# RK3399_RGMII_SDIO_SPI_GPIO.net
KiCad netlist of a schematic drawn in Altium Designer
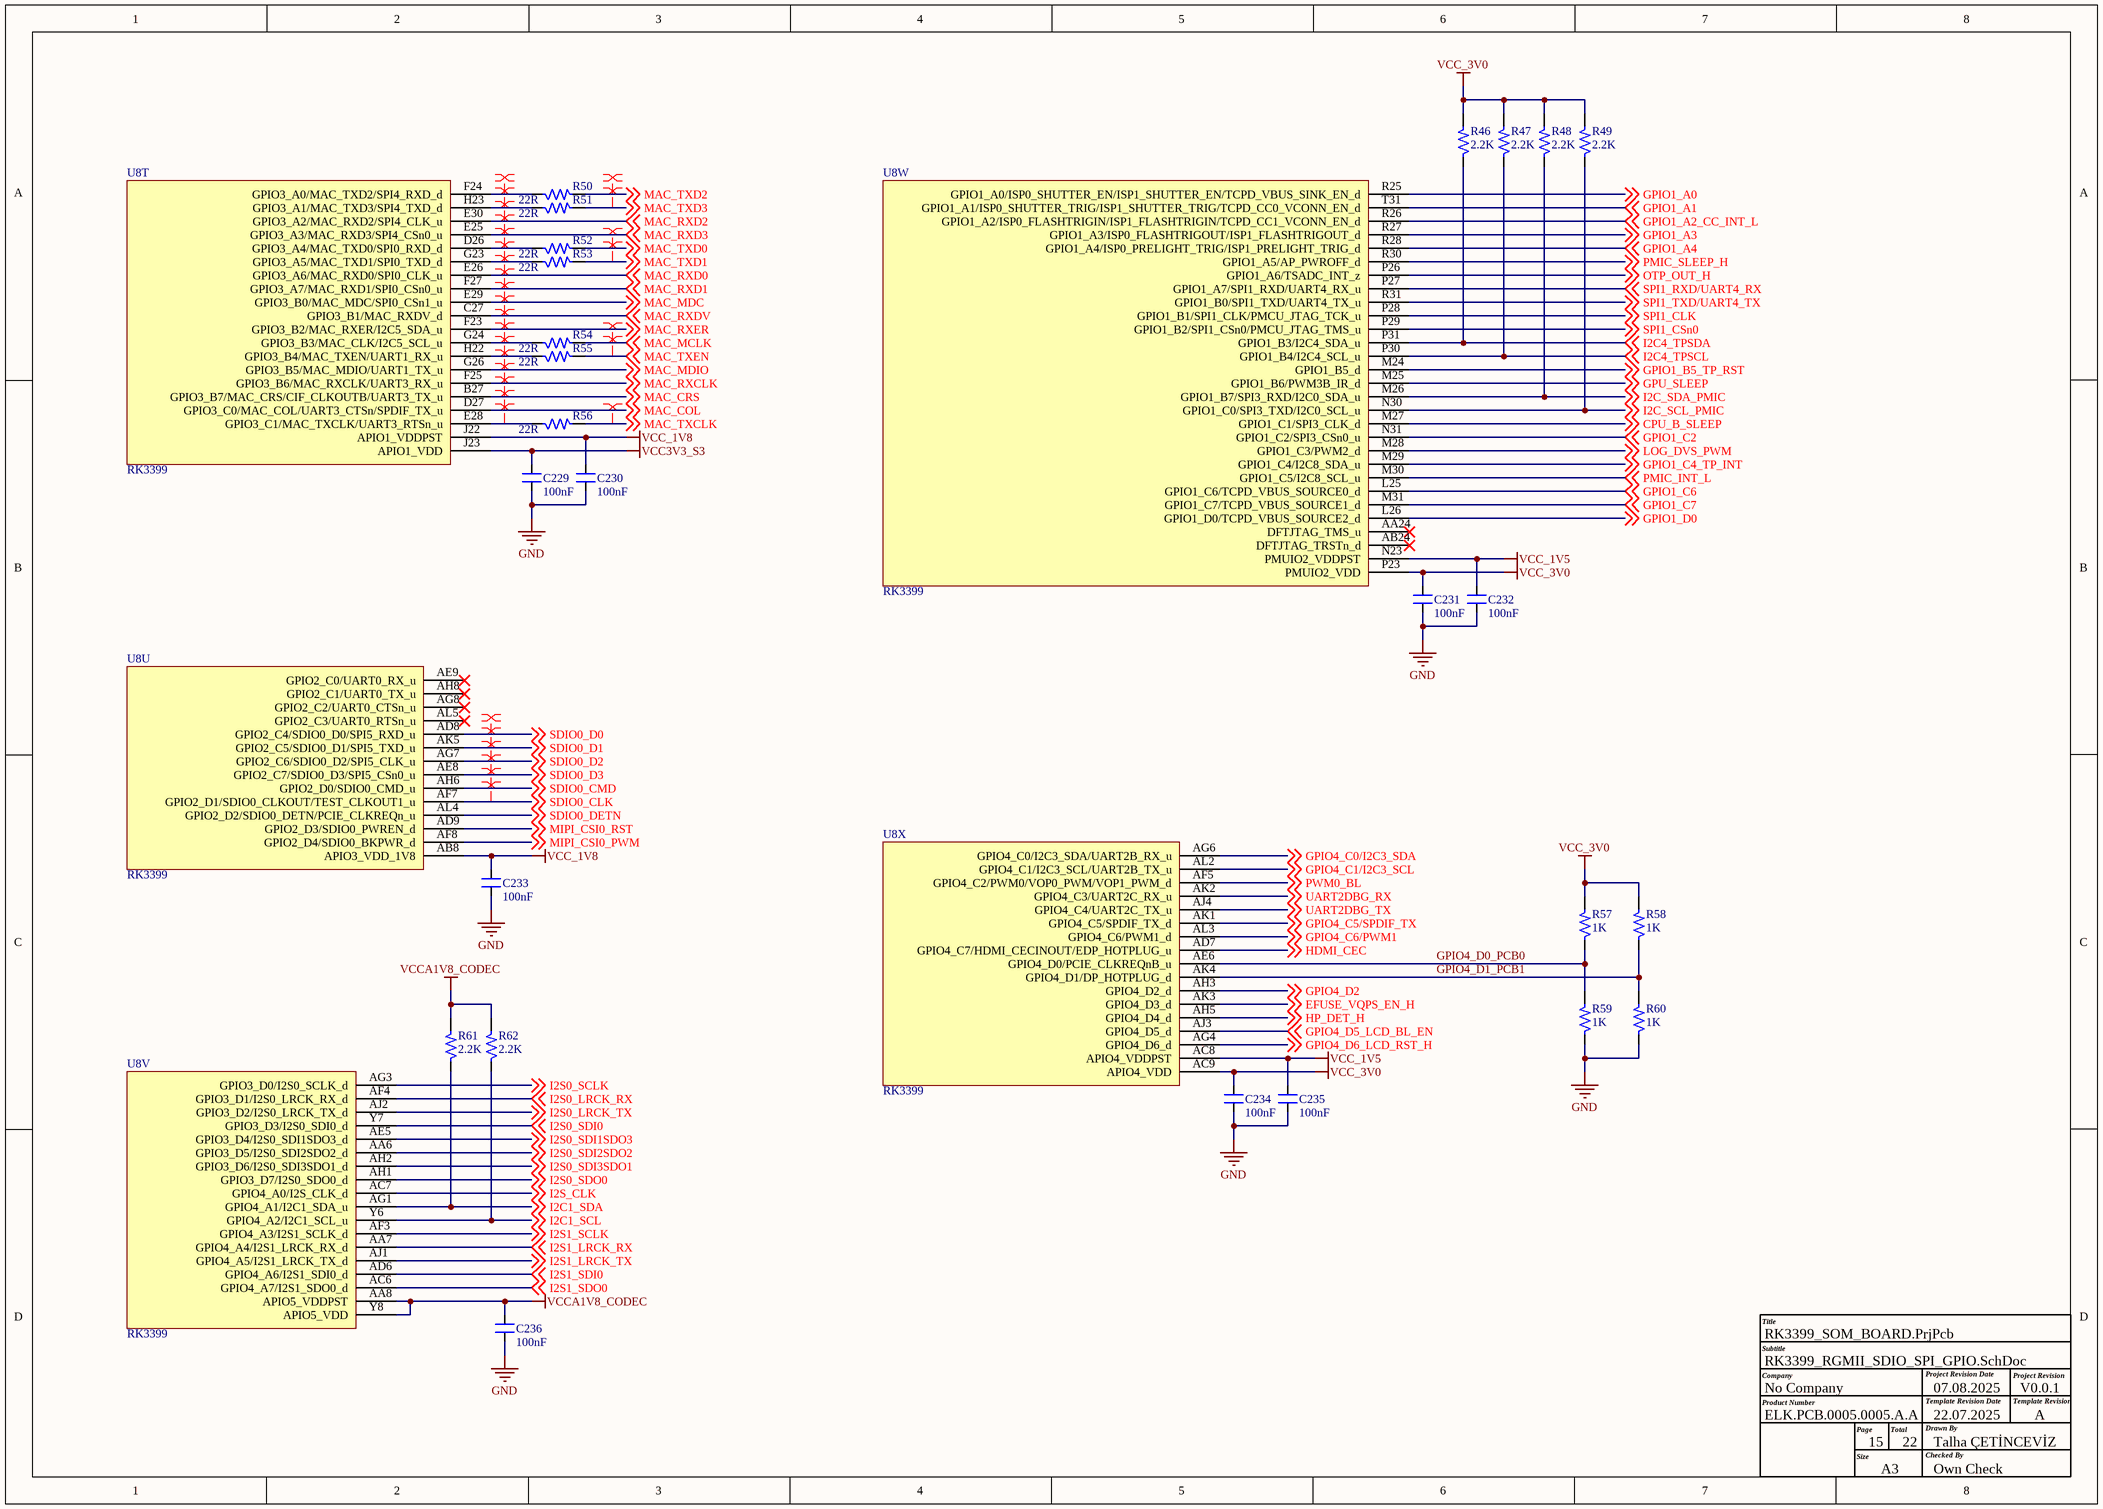
[diagram p0: RK3399_RGMII_SDIO_SPI_GPIO.SchDoc]

(export (version "E")
  (design (tool "Eeschema 10.0.6"))
  (components
    (comp (ref "C229")
      (value "100nF")
      (footprint "CAP_0201")
      (description "0.1µF ±10% 25V Ceramic Capacitor X5R 0201 (0603 Metric)")
      (fields
        (field (name "MANUFACTURER") "TDK Corporation")
        (field (name "MANUFACTURER PART NUMBER") "C0603X5R1E104K030BB")
      )
      (libsource (lib "EsteemPCB_SOM_Course_intlib") (part "CAP_100nF-25V-10%-0201"))
    )
    (comp (ref "C230")
      (value "100nF")
      (footprint "CAP_0201")
      (description "0.1µF ±10% 25V Ceramic Capacitor X5R 0201 (0603 Metric)")
      (fields
        (field (name "MANUFACTURER") "TDK Corporation")
        (field (name "MANUFACTURER PART NUMBER") "C0603X5R1E104K030BB")
      )
      (libsource (lib "EsteemPCB_SOM_Course_intlib") (part "CAP_100nF-25V-10%-0201"))
    )
    (comp (ref "C231")
      (value "100nF")
      (footprint "CAP_0201")
      (description "0.1µF ±10% 25V Ceramic Capacitor X5R 0201 (0603 Metric)")
      (fields
        (field (name "MANUFACTURER") "TDK Corporation")
        (field (name "MANUFACTURER PART NUMBER") "C0603X5R1E104K030BB")
      )
      (libsource (lib "EsteemPCB_SOM_Course_intlib") (part "CAP_100nF-25V-10%-0201"))
    )
    (comp (ref "C232")
      (value "100nF")
      (footprint "CAP_0201")
      (description "0.1µF ±10% 25V Ceramic Capacitor X5R 0201 (0603 Metric)")
      (fields
        (field (name "MANUFACTURER") "TDK Corporation")
        (field (name "MANUFACTURER PART NUMBER") "C0603X5R1E104K030BB")
      )
      (libsource (lib "EsteemPCB_SOM_Course_intlib") (part "CAP_100nF-25V-10%-0201"))
    )
    (comp (ref "C233")
      (value "100nF")
      (footprint "CAP_0201")
      (description "0.1µF ±10% 25V Ceramic Capacitor X5R 0201 (0603 Metric)")
      (fields
        (field (name "MANUFACTURER") "TDK Corporation")
        (field (name "MANUFACTURER PART NUMBER") "C0603X5R1E104K030BB")
      )
      (libsource (lib "EsteemPCB_SOM_Course_intlib") (part "CAP_100nF-25V-10%-0201"))
    )
    (comp (ref "C234")
      (value "100nF")
      (footprint "CAP_0201")
      (description "0.1µF ±10% 25V Ceramic Capacitor X5R 0201 (0603 Metric)")
      (fields
        (field (name "MANUFACTURER") "TDK Corporation")
        (field (name "MANUFACTURER PART NUMBER") "C0603X5R1E104K030BB")
      )
      (libsource (lib "EsteemPCB_SOM_Course_intlib") (part "CAP_100nF-25V-10%-0201"))
    )
    (comp (ref "C235")
      (value "100nF")
      (footprint "CAP_0201")
      (description "0.1µF ±10% 25V Ceramic Capacitor X5R 0201 (0603 Metric)")
      (fields
        (field (name "MANUFACTURER") "TDK Corporation")
        (field (name "MANUFACTURER PART NUMBER") "C0603X5R1E104K030BB")
      )
      (libsource (lib "EsteemPCB_SOM_Course_intlib") (part "CAP_100nF-25V-10%-0201"))
    )
    (comp (ref "C236")
      (value "100nF")
      (footprint "CAP_0201")
      (description "0.1µF ±10% 25V Ceramic Capacitor X5R 0201 (0603 Metric)")
      (fields
        (field (name "MANUFACTURER") "TDK Corporation")
        (field (name "MANUFACTURER PART NUMBER") "C0603X5R1E104K030BB")
      )
      (libsource (lib "EsteemPCB_SOM_Course_intlib") (part "CAP_100nF-25V-10%-0201"))
    )
    (comp (ref "R46")
      (value "2.2K")
      (footprint "RES_0201")
      (description "2.2 kOhms ±1% 0.05W, 1/20W Chip Resistor 0201 (0603 Metric) Thick Film")
      (fields
        (field (name "MANUFACTURER") "Stackpole Electronics Inc")
        (field (name "MANUFACTURER PART NUMBER") "RMCF0201FT2K20")
      )
      (libsource (lib "EsteemPCB_SOM_Course_intlib") (part "RES_2.2K-0.05W-1%-0201"))
    )
    (comp (ref "R47")
      (value "2.2K")
      (footprint "RES_0201")
      (description "2.2 kOhms ±1% 0.05W, 1/20W Chip Resistor 0201 (0603 Metric) Thick Film")
      (fields
        (field (name "MANUFACTURER") "Stackpole Electronics Inc")
        (field (name "MANUFACTURER PART NUMBER") "RMCF0201FT2K20")
      )
      (libsource (lib "EsteemPCB_SOM_Course_intlib") (part "RES_2.2K-0.05W-1%-0201"))
    )
    (comp (ref "R48")
      (value "2.2K")
      (footprint "RES_0201")
      (description "2.2 kOhms ±1% 0.05W, 1/20W Chip Resistor 0201 (0603 Metric) Thick Film")
      (fields
        (field (name "MANUFACTURER") "Stackpole Electronics Inc")
        (field (name "MANUFACTURER PART NUMBER") "RMCF0201FT2K20")
      )
      (libsource (lib "EsteemPCB_SOM_Course_intlib") (part "RES_2.2K-0.05W-1%-0201"))
    )
    (comp (ref "R49")
      (value "2.2K")
      (footprint "RES_0201")
      (description "2.2 kOhms ±1% 0.05W, 1/20W Chip Resistor 0201 (0603 Metric) Thick Film")
      (fields
        (field (name "MANUFACTURER") "Stackpole Electronics Inc")
        (field (name "MANUFACTURER PART NUMBER") "RMCF0201FT2K20")
      )
      (libsource (lib "EsteemPCB_SOM_Course_intlib") (part "RES_2.2K-0.05W-1%-0201"))
    )
    (comp (ref "R50")
      (value "22R")
      (footprint "RES_0201")
      (description "22 Ohms ±1% 0.05W, 1/20W Chip Resistor 0201 (0603 Metric) Moisture Resistant Thick Film")
      (fields
        (field (name "MANUFACTURER") "Yageo")
        (field (name "MANUFACTURER PART NUMBER") "RC0201FR-0722RL")
      )
      (libsource (lib "EsteemPCB_SOM_Course_intlib") (part "RES_22R-0.05W-1%-0201"))
    )
    (comp (ref "R51")
      (value "22R")
      (footprint "RES_0201")
      (description "22 Ohms ±1% 0.05W, 1/20W Chip Resistor 0201 (0603 Metric) Moisture Resistant Thick Film")
      (fields
        (field (name "MANUFACTURER") "Yageo")
        (field (name "MANUFACTURER PART NUMBER") "RC0201FR-0722RL")
      )
      (libsource (lib "EsteemPCB_SOM_Course_intlib") (part "RES_22R-0.05W-1%-0201"))
    )
    (comp (ref "R52")
      (value "22R")
      (footprint "RES_0201")
      (description "22 Ohms ±1% 0.05W, 1/20W Chip Resistor 0201 (0603 Metric) Moisture Resistant Thick Film")
      (fields
        (field (name "MANUFACTURER") "Yageo")
        (field (name "MANUFACTURER PART NUMBER") "RC0201FR-0722RL")
      )
      (libsource (lib "EsteemPCB_SOM_Course_intlib") (part "RES_22R-0.05W-1%-0201"))
    )
    (comp (ref "R53")
      (value "22R")
      (footprint "RES_0201")
      (description "22 Ohms ±1% 0.05W, 1/20W Chip Resistor 0201 (0603 Metric) Moisture Resistant Thick Film")
      (fields
        (field (name "MANUFACTURER") "Yageo")
        (field (name "MANUFACTURER PART NUMBER") "RC0201FR-0722RL")
      )
      (libsource (lib "EsteemPCB_SOM_Course_intlib") (part "RES_22R-0.05W-1%-0201"))
    )
    (comp (ref "R54")
      (value "22R")
      (footprint "RES_0201")
      (description "22 Ohms ±1% 0.05W, 1/20W Chip Resistor 0201 (0603 Metric) Moisture Resistant Thick Film")
      (fields
        (field (name "MANUFACTURER") "Yageo")
        (field (name "MANUFACTURER PART NUMBER") "RC0201FR-0722RL")
      )
      (libsource (lib "EsteemPCB_SOM_Course_intlib") (part "RES_22R-0.05W-1%-0201"))
    )
    (comp (ref "R55")
      (value "22R")
      (footprint "RES_0201")
      (description "22 Ohms ±1% 0.05W, 1/20W Chip Resistor 0201 (0603 Metric) Moisture Resistant Thick Film")
      (fields
        (field (name "MANUFACTURER") "Yageo")
        (field (name "MANUFACTURER PART NUMBER") "RC0201FR-0722RL")
      )
      (libsource (lib "EsteemPCB_SOM_Course_intlib") (part "RES_22R-0.05W-1%-0201"))
    )
    (comp (ref "R56")
      (value "22R")
      (footprint "RES_0201")
      (description "22 Ohms ±1% 0.05W, 1/20W Chip Resistor 0201 (0603 Metric) Moisture Resistant Thick Film")
      (fields
        (field (name "MANUFACTURER") "Yageo")
        (field (name "MANUFACTURER PART NUMBER") "RC0201FR-0722RL")
      )
      (libsource (lib "EsteemPCB_SOM_Course_intlib") (part "RES_22R-0.05W-1%-0201"))
    )
    (comp (ref "R57")
      (value "1K")
      (footprint "RES_0201")
      (description "1 kOhms ±1% 0.05W, 1/20W Chip Resistor 0201 (0603 Metric) Thick Film")
      (fields
        (field (name "MANUFACTURER") "Yageo")
        (field (name "MANUFACTURER PART NUMBER") "RC0201FR-071KL")
      )
      (libsource (lib "EsteemPCB_SOM_Course_intlib") (part "RES_1K-0.05W-1%-0201"))
    )
    (comp (ref "R58")
      (value "1K")
      (footprint "RES_0201")
      (description "1 kOhms ±1% 0.05W, 1/20W Chip Resistor 0201 (0603 Metric) Thick Film")
      (fields
        (field (name "MANUFACTURER") "Yageo")
        (field (name "MANUFACTURER PART NUMBER") "RC0201FR-071KL")
      )
      (libsource (lib "EsteemPCB_SOM_Course_intlib") (part "RES_1K-0.05W-1%-0201"))
    )
    (comp (ref "R59")
      (value "1K")
      (footprint "RES_0201")
      (description "1 kOhms ±1% 0.05W, 1/20W Chip Resistor 0201 (0603 Metric) Thick Film")
      (fields
        (field (name "MANUFACTURER") "Yageo")
        (field (name "MANUFACTURER PART NUMBER") "RC0201FR-071KL")
      )
      (libsource (lib "EsteemPCB_SOM_Course_intlib") (part "RES_1K-0.05W-1%-0201"))
    )
    (comp (ref "R60")
      (value "1K")
      (footprint "RES_0201")
      (description "1 kOhms ±1% 0.05W, 1/20W Chip Resistor 0201 (0603 Metric) Thick Film")
      (fields
        (field (name "MANUFACTURER") "Yageo")
        (field (name "MANUFACTURER PART NUMBER") "RC0201FR-071KL")
      )
      (libsource (lib "EsteemPCB_SOM_Course_intlib") (part "RES_1K-0.05W-1%-0201"))
    )
    (comp (ref "R61")
      (value "2.2K")
      (footprint "RES_0201")
      (description "2.2 kOhms ±1% 0.05W, 1/20W Chip Resistor 0201 (0603 Metric) Thick Film")
      (fields
        (field (name "MANUFACTURER") "Stackpole Electronics Inc")
        (field (name "MANUFACTURER PART NUMBER") "RMCF0201FT2K20")
      )
      (libsource (lib "EsteemPCB_SOM_Course_intlib") (part "RES_2.2K-0.05W-1%-0201"))
    )
    (comp (ref "R62")
      (value "2.2K")
      (footprint "RES_0201")
      (description "2.2 kOhms ±1% 0.05W, 1/20W Chip Resistor 0201 (0603 Metric) Thick Film")
      (fields
        (field (name "MANUFACTURER") "Stackpole Electronics Inc")
        (field (name "MANUFACTURER PART NUMBER") "RMCF0201FT2K20")
      )
      (libsource (lib "EsteemPCB_SOM_Course_intlib") (part "RES_2.2K-0.05W-1%-0201"))
    )
    (comp (ref "U8")
      (value "RK3399")
      (footprint "FBGA828_23_826X826")
      (description "RK3399 is a low power, high performance processor for computing, personal mobile.")
      (fields (field (name "MANUFACTURER") "Rockchip"))
      (libsource (lib "EsteemPCB_SOM_Course_intlib") (part "IC_RK3399-FCBGA828"))
    )
  )
  (nets
    (net (code "1") (name "/GPIO4_D0_PCB0") (class "Default")
      (node (ref "R57") (pin "1") (pinfunction "1_1") (pintype "passive"))
      (node (ref "R59") (pin "2") (pinfunction "2_2") (pintype "passive"))
      (node (ref "U8") (pin "AE6") (pinfunction "GPIO4_D0/PCIE_CLKREQnB_u_AE6") (pintype "passive"))
    )
    (net (code "2") (name "/GPIO4_D1_PCB1") (class "Default")
      (node (ref "R58") (pin "1") (pinfunction "1_1") (pintype "passive"))
      (node (ref "R60") (pin "2") (pinfunction "2_2") (pintype "passive"))
      (node (ref "U8") (pin "AK4") (pinfunction "GPIO4_D1/DP_HOTPLUG_d_AK4") (pintype "passive"))
    )
    (net (code "3") (name "CPU_B_SLEEP") (class "Default")
      (node (ref "U8") (pin "M27") (pinfunction "GPIO1_C1/SPI3_CLK_d_M27") (pintype "passive"))
    )
    (net (code "4") (name "EFUSE_VQPS_EN_H") (class "Default")
      (node (ref "U8") (pin "AK3") (pinfunction "GPIO4_D3_d_AK3") (pintype "passive"))
    )
    (net (code "5") (name "GND") (class "Default")
      (node (ref "C229") (pin "1") (pinfunction "1_1") (pintype "passive"))
      (node (ref "C230") (pin "1") (pinfunction "1_1") (pintype "passive"))
      (node (ref "C231") (pin "1") (pinfunction "1_1") (pintype "passive"))
      (node (ref "C232") (pin "1") (pinfunction "1_1") (pintype "passive"))
      (node (ref "C233") (pin "1") (pinfunction "1_1") (pintype "passive"))
      (node (ref "C234") (pin "1") (pinfunction "1_1") (pintype "passive"))
      (node (ref "C235") (pin "1") (pinfunction "1_1") (pintype "passive"))
      (node (ref "C236") (pin "1") (pinfunction "1_1") (pintype "passive"))
      (node (ref "R59") (pin "1") (pinfunction "1_1") (pintype "passive"))
      (node (ref "R60") (pin "1") (pinfunction "1_1") (pintype "passive"))
    )
    (net (code "6") (name "GPIO1_A0") (class "Default")
      (node (ref "U8") (pin "R25") (pinfunction "GPIO1_A0/ISP0_SHUTTER_EN/ISP1_SHUTTER_EN/TCPD_VBUS_SINK_EN_d_R25") (pintype "passive"))
    )
    (net (code "7") (name "GPIO1_A1") (class "Default")
      (node (ref "U8") (pin "T31") (pinfunction "GPIO1_A1/ISP0_SHUTTER_TRIG/ISP1_SHUTTER_TRIG/TCPD_CC0_VCONN_EN_d_T31") (pintype "passive"))
    )
    (net (code "8") (name "GPIO1_A2_CC_INT_L") (class "Default")
      (node (ref "U8") (pin "R26") (pinfunction "GPIO1_A2/ISP0_FLASHTRIGIN/ISP1_FLASHTRIGIN/TCPD_CC1_VCONN_EN_d_R26") (pintype "passive"))
    )
    (net (code "9") (name "GPIO1_A3") (class "Default")
      (node (ref "U8") (pin "R27") (pinfunction "GPIO1_A3/ISP0_FLASHTRIGOUT/ISP1_FLASHTRIGOUT_d_R27") (pintype "passive"))
    )
    (net (code "10") (name "GPIO1_A4") (class "Default")
      (node (ref "U8") (pin "R28") (pinfunction "GPIO1_A4/ISP0_PRELIGHT_TRIG/ISP1_PRELIGHT_TRIG_d_R28") (pintype "passive"))
    )
    (net (code "11") (name "GPIO1_B5_TP_RST") (class "Default")
      (node (ref "U8") (pin "M24") (pinfunction "GPIO1_B5_d_M24") (pintype "passive"))
    )
    (net (code "12") (name "GPIO1_C2") (class "Default")
      (node (ref "U8") (pin "N31") (pinfunction "GPIO1_C2/SPI3_CSn0_u_N31") (pintype "passive"))
    )
    (net (code "13") (name "GPIO1_C4_TP_INT") (class "Default")
      (node (ref "U8") (pin "M29") (pinfunction "GPIO1_C4/I2C8_SDA_u_M29") (pintype "passive"))
    )
    (net (code "14") (name "GPIO1_C6") (class "Default")
      (node (ref "U8") (pin "L25") (pinfunction "GPIO1_C6/TCPD_VBUS_SOURCE0_d_L25") (pintype "passive"))
    )
    (net (code "15") (name "GPIO1_C7") (class "Default")
      (node (ref "U8") (pin "M31") (pinfunction "GPIO1_C7/TCPD_VBUS_SOURCE1_d_M31") (pintype "passive"))
    )
    (net (code "16") (name "GPIO1_D0") (class "Default")
      (node (ref "U8") (pin "L26") (pinfunction "GPIO1_D0/TCPD_VBUS_SOURCE2_d_L26") (pintype "passive"))
    )
    (net (code "17") (name "GPIO4_C0{slash}I2C3_SDA") (class "Default")
      (node (ref "U8") (pin "AG6") (pinfunction "GPIO4_C0/I2C3_SDA/UART2B_RX_u_AG6") (pintype "passive"))
    )
    (net (code "18") (name "GPIO4_C1{slash}I2C3_SCL") (class "Default")
      (node (ref "U8") (pin "AL2") (pinfunction "GPIO4_C1/I2C3_SCL/UART2B_TX_u_AL2") (pintype "passive"))
    )
    (net (code "19") (name "GPIO4_C5{slash}SPDIF_TX") (class "Default")
      (node (ref "U8") (pin "AK1") (pinfunction "GPIO4_C5/SPDIF_TX_d_AK1") (pintype "passive"))
    )
    (net (code "20") (name "GPIO4_C6{slash}PWM1") (class "Default")
      (node (ref "U8") (pin "AL3") (pinfunction "GPIO4_C6/PWM1_d_AL3") (pintype "passive"))
    )
    (net (code "21") (name "GPIO4_D2") (class "Default")
      (node (ref "U8") (pin "AH3") (pinfunction "GPIO4_D2_d_AH3") (pintype "passive"))
    )
    (net (code "22") (name "GPIO4_D5_LCD_BL_EN") (class "Default")
      (node (ref "U8") (pin "AJ3") (pinfunction "GPIO4_D5_d_AJ3") (pintype "passive"))
    )
    (net (code "23") (name "GPIO4_D6_LCD_RST_H") (class "Default")
      (node (ref "U8") (pin "AG4") (pinfunction "GPIO4_D6_d_AG4") (pintype "passive"))
    )
    (net (code "24") (name "GPU_SLEEP") (class "Default")
      (node (ref "U8") (pin "M25") (pinfunction "GPIO1_B6/PWM3B_IR_d_M25") (pintype "passive"))
    )
    (net (code "25") (name "HDMI_CEC") (class "Default")
      (node (ref "U8") (pin "AD7") (pinfunction "GPIO4_C7/HDMI_CECINOUT/EDP_HOTPLUG_u_AD7") (pintype "passive"))
    )
    (net (code "26") (name "HP_DET_H") (class "Default")
      (node (ref "U8") (pin "AH5") (pinfunction "GPIO4_D4_d_AH5") (pintype "passive"))
    )
    (net (code "27") (name "I2C1_SCL") (class "Default")
      (node (ref "R62") (pin "1") (pinfunction "1_1") (pintype "passive"))
      (node (ref "U8") (pin "Y6") (pinfunction "GPIO4_A2/I2C1_SCL_u_Y6") (pintype "passive"))
    )
    (net (code "28") (name "I2C1_SDA") (class "Default")
      (node (ref "R61") (pin "1") (pinfunction "1_1") (pintype "passive"))
      (node (ref "U8") (pin "AG1") (pinfunction "GPIO4_A1/I2C1_SDA_u_AG1") (pintype "passive"))
    )
    (net (code "29") (name "I2C4_TPSCL") (class "Default")
      (node (ref "R47") (pin "1") (pinfunction "1_1") (pintype "passive"))
      (node (ref "U8") (pin "P30") (pinfunction "GPIO1_B4/I2C4_SCL_u_P30") (pintype "passive"))
    )
    (net (code "30") (name "I2C4_TPSDA") (class "Default")
      (node (ref "R46") (pin "1") (pinfunction "1_1") (pintype "passive"))
      (node (ref "U8") (pin "P31") (pinfunction "GPIO1_B3/I2C4_SDA_u_P31") (pintype "passive"))
    )
    (net (code "31") (name "I2C_SCL_PMIC") (class "Default")
      (node (ref "R49") (pin "1") (pinfunction "1_1") (pintype "passive"))
      (node (ref "U8") (pin "N30") (pinfunction "GPIO1_C0/SPI3_TXD/I2C0_SCL_u_N30") (pintype "passive"))
    )
    (net (code "32") (name "I2C_SDA_PMIC") (class "Default")
      (node (ref "R48") (pin "1") (pinfunction "1_1") (pintype "passive"))
      (node (ref "U8") (pin "M26") (pinfunction "GPIO1_B7/SPI3_RXD/I2C0_SDA_u_M26") (pintype "passive"))
    )
    (net (code "33") (name "I2S0_LRCK_RX") (class "Default")
      (node (ref "U8") (pin "AF4") (pinfunction "GPIO3_D1/I2S0_LRCK_RX_d_AF4") (pintype "passive"))
    )
    (net (code "34") (name "I2S0_LRCK_TX") (class "Default")
      (node (ref "U8") (pin "AJ2") (pinfunction "GPIO3_D2/I2S0_LRCK_TX_d_AJ2") (pintype "passive"))
    )
    (net (code "35") (name "I2S0_SCLK") (class "Default")
      (node (ref "U8") (pin "AG3") (pinfunction "GPIO3_D0/I2S0_SCLK_d_AG3") (pintype "passive"))
    )
    (net (code "36") (name "I2S0_SDI0") (class "Default")
      (node (ref "U8") (pin "Y7") (pinfunction "GPIO3_D3/I2S0_SDI0_d_Y7") (pintype "passive"))
    )
    (net (code "37") (name "I2S0_SDI1SDO3") (class "Default")
      (node (ref "U8") (pin "AE5") (pinfunction "GPIO3_D4/I2S0_SDI1SDO3_d_AE5") (pintype "passive"))
    )
    (net (code "38") (name "I2S0_SDI2SDO2") (class "Default")
      (node (ref "U8") (pin "AA6") (pinfunction "GPIO3_D5/I2S0_SDI2SDO2_d_AA6") (pintype "passive"))
    )
    (net (code "39") (name "I2S0_SDI3SDO1") (class "Default")
      (node (ref "U8") (pin "AH2") (pinfunction "GPIO3_D6/I2S0_SDI3SDO1_d_AH2") (pintype "passive"))
    )
    (net (code "40") (name "I2S0_SDO0") (class "Default")
      (node (ref "U8") (pin "AH1") (pinfunction "GPIO3_D7/I2S0_SDO0_d_AH1") (pintype "passive"))
    )
    (net (code "41") (name "I2S1_LRCK_RX") (class "Default")
      (node (ref "U8") (pin "AA7") (pinfunction "GPIO4_A4/I2S1_LRCK_RX_d_AA7") (pintype "passive"))
    )
    (net (code "42") (name "I2S1_LRCK_TX") (class "Default")
      (node (ref "U8") (pin "AJ1") (pinfunction "GPIO4_A5/I2S1_LRCK_TX_d_AJ1") (pintype "passive"))
    )
    (net (code "43") (name "I2S1_SCLK") (class "Default")
      (node (ref "U8") (pin "AF3") (pinfunction "GPIO4_A3/I2S1_SCLK_d_AF3") (pintype "passive"))
    )
    (net (code "44") (name "I2S1_SDI0") (class "Default")
      (node (ref "U8") (pin "AD6") (pinfunction "GPIO4_A6/I2S1_SDI0_d_AD6") (pintype "passive"))
    )
    (net (code "45") (name "I2S1_SDO0") (class "Default")
      (node (ref "U8") (pin "AC6") (pinfunction "GPIO4_A7/I2S1_SDO0_d_AC6") (pintype "passive"))
    )
    (net (code "46") (name "I2S_CLK") (class "Default")
      (node (ref "U8") (pin "AC7") (pinfunction "GPIO4_A0/I2S_CLK_d_AC7") (pintype "passive"))
    )
    (net (code "47") (name "LOG_DVS_PWM") (class "Default")
      (node (ref "U8") (pin "M28") (pinfunction "GPIO1_C3/PWM2_d_M28") (pintype "passive"))
    )
    (net (code "48") (name "MAC_COL") (class "Default")
      (node (ref "U8") (pin "D27") (pinfunction "GPIO3_C0/MAC_COL/UART3_CTSn/SPDIF_TX_u_D27") (pintype "passive"))
    )
    (net (code "49") (name "MAC_CRS") (class "Default")
      (node (ref "U8") (pin "B27") (pinfunction "GPIO3_B7/MAC_CRS/CIF_CLKOUTB/UART3_TX_u_B27") (pintype "passive"))
    )
    (net (code "50") (name "MAC_MCLK") (class "Default")
      (node (ref "R54") (pin "2") (pinfunction "2_2") (pintype "passive"))
    )
    (net (code "51") (name "MAC_MDC") (class "Default")
      (node (ref "U8") (pin "E29") (pinfunction "GPIO3_B0/MAC_MDC/SPI0_CSn1_u_E29") (pintype "passive"))
    )
    (net (code "52") (name "MAC_MDIO") (class "Default")
      (node (ref "U8") (pin "G26") (pinfunction "GPIO3_B5/MAC_MDIO/UART1_TX_u_G26") (pintype "passive"))
    )
    (net (code "53") (name "MAC_RXCLK") (class "Default")
      (node (ref "U8") (pin "F25") (pinfunction "GPIO3_B6/MAC_RXCLK/UART3_RX_u_F25") (pintype "passive"))
    )
    (net (code "54") (name "MAC_RXD0") (class "Default")
      (node (ref "U8") (pin "E26") (pinfunction "GPIO3_A6/MAC_RXD0/SPI0_CLK_u_E26") (pintype "passive"))
    )
    (net (code "55") (name "MAC_RXD1") (class "Default")
      (node (ref "U8") (pin "F27") (pinfunction "GPIO3_A7/MAC_RXD1/SPI0_CSn0_u_F27") (pintype "passive"))
    )
    (net (code "56") (name "MAC_RXD2") (class "Default")
      (node (ref "U8") (pin "E30") (pinfunction "GPIO3_A2/MAC_RXD2/SPI4_CLK_u_E30") (pintype "passive"))
    )
    (net (code "57") (name "MAC_RXD3") (class "Default")
      (node (ref "U8") (pin "E25") (pinfunction "GPIO3_A3/MAC_RXD3/SPI4_CSn0_u_E25") (pintype "passive"))
    )
    (net (code "58") (name "MAC_RXDV") (class "Default")
      (node (ref "U8") (pin "C27") (pinfunction "GPIO3_B1/MAC_RXDV_d_C27") (pintype "passive"))
    )
    (net (code "59") (name "MAC_RXER") (class "Default")
      (node (ref "U8") (pin "F23") (pinfunction "GPIO3_B2/MAC_RXER/I2C5_SDA_u_F23") (pintype "passive"))
    )
    (net (code "60") (name "MAC_TXCLK") (class "Default")
      (node (ref "R56") (pin "2") (pinfunction "2_2") (pintype "passive"))
    )
    (net (code "61") (name "MAC_TXD0") (class "Default")
      (node (ref "R52") (pin "2") (pinfunction "2_2") (pintype "passive"))
    )
    (net (code "62") (name "MAC_TXD1") (class "Default")
      (node (ref "R53") (pin "2") (pinfunction "2_2") (pintype "passive"))
    )
    (net (code "63") (name "MAC_TXD2") (class "Default")
      (node (ref "R50") (pin "2") (pinfunction "2_2") (pintype "passive"))
    )
    (net (code "64") (name "MAC_TXD3") (class "Default")
      (node (ref "R51") (pin "2") (pinfunction "2_2") (pintype "passive"))
    )
    (net (code "65") (name "MAC_TXEN") (class "Default")
      (node (ref "R55") (pin "2") (pinfunction "2_2") (pintype "passive"))
    )
    (net (code "66") (name "MIPI_CSI0_PWM") (class "Default")
      (node (ref "U8") (pin "AF8") (pinfunction "GPIO2_D4/SDIO0_BKPWR_d_AF8") (pintype "passive"))
    )
    (net (code "67") (name "MIPI_CSI0_RST") (class "Default")
      (node (ref "U8") (pin "AD9") (pinfunction "GPIO2_D3/SDIO0_PWREN_d_AD9") (pintype "passive"))
    )
    (net (code "68") (name "Net-(U8T-GPIO3_A0{slash}MAC_TXD2{slash}SPI4_RXD_d)") (class "Default")
      (node (ref "R50") (pin "1") (pinfunction "1_1") (pintype "passive"))
      (node (ref "U8") (pin "F24") (pinfunction "GPIO3_A0/MAC_TXD2/SPI4_RXD_d_F24") (pintype "passive"))
    )
    (net (code "69") (name "Net-(U8T-GPIO3_A1{slash}MAC_TXD3{slash}SPI4_TXD_d)") (class "Default")
      (node (ref "R51") (pin "1") (pinfunction "1_1") (pintype "passive"))
      (node (ref "U8") (pin "H23") (pinfunction "GPIO3_A1/MAC_TXD3/SPI4_TXD_d_H23") (pintype "passive"))
    )
    (net (code "70") (name "Net-(U8T-GPIO3_A4{slash}MAC_TXD0{slash}SPI0_RXD_d)") (class "Default")
      (node (ref "R52") (pin "1") (pinfunction "1_1") (pintype "passive"))
      (node (ref "U8") (pin "D26") (pinfunction "GPIO3_A4/MAC_TXD0/SPI0_RXD_d_D26") (pintype "passive"))
    )
    (net (code "71") (name "Net-(U8T-GPIO3_A5{slash}MAC_TXD1{slash}SPI0_TXD_d)") (class "Default")
      (node (ref "R53") (pin "1") (pinfunction "1_1") (pintype "passive"))
      (node (ref "U8") (pin "G23") (pinfunction "GPIO3_A5/MAC_TXD1/SPI0_TXD_d_G23") (pintype "passive"))
    )
    (net (code "72") (name "Net-(U8T-GPIO3_B3{slash}MAC_CLK{slash}I2C5_SCL_u)") (class "Default")
      (node (ref "R54") (pin "1") (pinfunction "1_1") (pintype "passive"))
      (node (ref "U8") (pin "G24") (pinfunction "GPIO3_B3/MAC_CLK/I2C5_SCL_u_G24") (pintype "passive"))
    )
    (net (code "73") (name "Net-(U8T-GPIO3_B4{slash}MAC_TXEN{slash}UART1_RX_u)") (class "Default")
      (node (ref "R55") (pin "1") (pinfunction "1_1") (pintype "passive"))
      (node (ref "U8") (pin "H22") (pinfunction "GPIO3_B4/MAC_TXEN/UART1_RX_u_H22") (pintype "passive"))
    )
    (net (code "74") (name "Net-(U8T-GPIO3_C1{slash}MAC_TXCLK{slash}UART3_RTSn_u)") (class "Default")
      (node (ref "R56") (pin "1") (pinfunction "1_1") (pintype "passive"))
      (node (ref "U8") (pin "E28") (pinfunction "GPIO3_C1/MAC_TXCLK/UART3_RTSn_u_E28") (pintype "passive"))
    )
    (net (code "75") (name "OTP_OUT_H") (class "Default")
      (node (ref "U8") (pin "P26") (pinfunction "GPIO1_A6/TSADC_INT_z_P26") (pintype "passive"))
    )
    (net (code "76") (name "PMIC_INT_L") (class "Default")
      (node (ref "U8") (pin "M30") (pinfunction "GPIO1_C5/I2C8_SCL_u_M30") (pintype "passive"))
    )
    (net (code "77") (name "PMIC_SLEEP_H") (class "Default")
      (node (ref "U8") (pin "R30") (pinfunction "GPIO1_A5/AP_PWROFF_d_R30") (pintype "passive"))
    )
    (net (code "78") (name "PWM0_BL") (class "Default")
      (node (ref "U8") (pin "AF5") (pinfunction "GPIO4_C2/PWM0/VOP0_PWM/VOP1_PWM_d_AF5") (pintype "passive"))
    )
    (net (code "79") (name "SDIO0_CLK") (class "Default")
      (node (ref "U8") (pin "AF7") (pinfunction "GPIO2_D1/SDIO0_CLKOUT/TEST_CLKOUT1_u_AF7") (pintype "passive"))
    )
    (net (code "80") (name "SDIO0_CMD") (class "Default")
      (node (ref "U8") (pin "AH6") (pinfunction "GPIO2_D0/SDIO0_CMD_u_AH6") (pintype "passive"))
    )
    (net (code "81") (name "SDIO0_D0") (class "Default")
      (node (ref "U8") (pin "AD8") (pinfunction "GPIO2_C4/SDIO0_D0/SPI5_RXD_u_AD8") (pintype "passive"))
    )
    (net (code "82") (name "SDIO0_D1") (class "Default")
      (node (ref "U8") (pin "AK5") (pinfunction "GPIO2_C5/SDIO0_D1/SPI5_TXD_u_AK5") (pintype "passive"))
    )
    (net (code "83") (name "SDIO0_D2") (class "Default")
      (node (ref "U8") (pin "AG7") (pinfunction "GPIO2_C6/SDIO0_D2/SPI5_CLK_u_AG7") (pintype "passive"))
    )
    (net (code "84") (name "SDIO0_D3") (class "Default")
      (node (ref "U8") (pin "AE8") (pinfunction "GPIO2_C7/SDIO0_D3/SPI5_CSn0_u_AE8") (pintype "passive"))
    )
    (net (code "85") (name "SDIO0_DETN") (class "Default")
      (node (ref "U8") (pin "AL4") (pinfunction "GPIO2_D2/SDIO0_DETN/PCIE_CLKREQn_u_AL4") (pintype "passive"))
    )
    (net (code "86") (name "SPI1_CLK") (class "Default")
      (node (ref "U8") (pin "P28") (pinfunction "GPIO1_B1/SPI1_CLK/PMCU_JTAG_TCK_u_P28") (pintype "passive"))
    )
    (net (code "87") (name "SPI1_CSn0") (class "Default")
      (node (ref "U8") (pin "P29") (pinfunction "GPIO1_B2/SPI1_CSn0/PMCU_JTAG_TMS_u_P29") (pintype "passive"))
    )
    (net (code "88") (name "SPI1_RXD{slash}UART4_RX") (class "Default")
      (node (ref "U8") (pin "P27") (pinfunction "GPIO1_A7/SPI1_RXD/UART4_RX_u_P27") (pintype "passive"))
    )
    (net (code "89") (name "SPI1_TXD{slash}UART4_TX") (class "Default")
      (node (ref "U8") (pin "R31") (pinfunction "GPIO1_B0/SPI1_TXD/UART4_TX_u_R31") (pintype "passive"))
    )
    (net (code "90") (name "UART2DBG_RX") (class "Default")
      (node (ref "U8") (pin "AK2") (pinfunction "GPIO4_C3/UART2C_RX_u_AK2") (pintype "passive"))
    )
    (net (code "91") (name "UART2DBG_TX") (class "Default")
      (node (ref "U8") (pin "AJ4") (pinfunction "GPIO4_C4/UART2C_TX_u_AJ4") (pintype "passive"))
    )
    (net (code "92") (name "VCC3V3_S3") (class "Default")
      (node (ref "C229") (pin "2") (pinfunction "2_2") (pintype "passive"))
      (node (ref "U8") (pin "J23") (pinfunction "APIO1_VDD_J23") (pintype "passive"))
    )
    (net (code "93") (name "VCCA1V8_CODEC") (class "Default")
      (node (ref "C236") (pin "2") (pinfunction "2_2") (pintype "passive"))
      (node (ref "R61") (pin "2") (pinfunction "2_2") (pintype "passive"))
      (node (ref "R62") (pin "2") (pinfunction "2_2") (pintype "passive"))
      (node (ref "U8") (pin "AA8") (pinfunction "APIO5_VDDPST_AA8") (pintype "passive"))
      (node (ref "U8") (pin "Y8") (pinfunction "APIO5_VDD_Y8") (pintype "passive"))
    )
    (net (code "94") (name "VCC_1V5") (class "Default")
      (node (ref "C232") (pin "2") (pinfunction "2_2") (pintype "passive"))
      (node (ref "C235") (pin "2") (pinfunction "2_2") (pintype "passive"))
      (node (ref "U8") (pin "AC8") (pinfunction "APIO4_VDDPST_AC8") (pintype "passive"))
      (node (ref "U8") (pin "N23") (pinfunction "PMUIO2_VDDPST_N23") (pintype "passive"))
    )
    (net (code "95") (name "VCC_1V8") (class "Default")
      (node (ref "C230") (pin "2") (pinfunction "2_2") (pintype "passive"))
      (node (ref "C233") (pin "2") (pinfunction "2_2") (pintype "passive"))
      (node (ref "U8") (pin "AB8") (pinfunction "APIO3_VDD_1V8_AB8") (pintype "passive"))
      (node (ref "U8") (pin "J22") (pinfunction "APIO1_VDDPST_J22") (pintype "passive"))
    )
    (net (code "96") (name "VCC_3V0") (class "Default")
      (node (ref "C231") (pin "2") (pinfunction "2_2") (pintype "passive"))
      (node (ref "C234") (pin "2") (pinfunction "2_2") (pintype "passive"))
      (node (ref "R46") (pin "2") (pinfunction "2_2") (pintype "passive"))
      (node (ref "R47") (pin "2") (pinfunction "2_2") (pintype "passive"))
      (node (ref "R48") (pin "2") (pinfunction "2_2") (pintype "passive"))
      (node (ref "R49") (pin "2") (pinfunction "2_2") (pintype "passive"))
      (node (ref "R57") (pin "2") (pinfunction "2_2") (pintype "passive"))
      (node (ref "R58") (pin "2") (pinfunction "2_2") (pintype "passive"))
      (node (ref "U8") (pin "AC9") (pinfunction "APIO4_VDD_AC9") (pintype "passive"))
      (node (ref "U8") (pin "P23") (pinfunction "PMUIO2_VDD_P23") (pintype "passive"))
    )
    (net (code "97") (name "unconnected-(U8U-GPIO2_C0{slash}UART0_RX_u-PadAE9)") (class "Default")
      (node (ref "U8") (pin "AE9") (pinfunction "GPIO2_C0/UART0_RX_u_AE9") (pintype "passive+no_connect"))
    )
    (net (code "98") (name "unconnected-(U8U-GPIO2_C1{slash}UART0_TX_u-PadAH8)") (class "Default")
      (node (ref "U8") (pin "AH8") (pinfunction "GPIO2_C1/UART0_TX_u_AH8") (pintype "passive+no_connect"))
    )
    (net (code "99") (name "unconnected-(U8U-GPIO2_C2{slash}UART0_CTSn_u-PadAG8)") (class "Default")
      (node (ref "U8") (pin "AG8") (pinfunction "GPIO2_C2/UART0_CTSn_u_AG8") (pintype "passive+no_connect"))
    )
    (net (code "100") (name "unconnected-(U8U-GPIO2_C3{slash}UART0_RTSn_u-PadAL5)") (class "Default")
      (node (ref "U8") (pin "AL5") (pinfunction "GPIO2_C3/UART0_RTSn_u_AL5") (pintype "passive+no_connect"))
    )
    (net (code "101") (name "unconnected-(U8W-DFTJTAG_TMS_u-PadAA24)") (class "Default")
      (node (ref "U8") (pin "AA24") (pinfunction "DFTJTAG_TMS_u_AA24") (pintype "passive+no_connect"))
    )
    (net (code "102") (name "unconnected-(U8W-DFTJTAG_TRSTn_d-PadAB24)") (class "Default")
      (node (ref "U8") (pin "AB24") (pinfunction "DFTJTAG_TRSTn_d_AB24") (pintype "passive+no_connect"))
    )
  )
)
